# Annealer_PCB.net
KiCad netlist of a schematic drawn in EAGLE
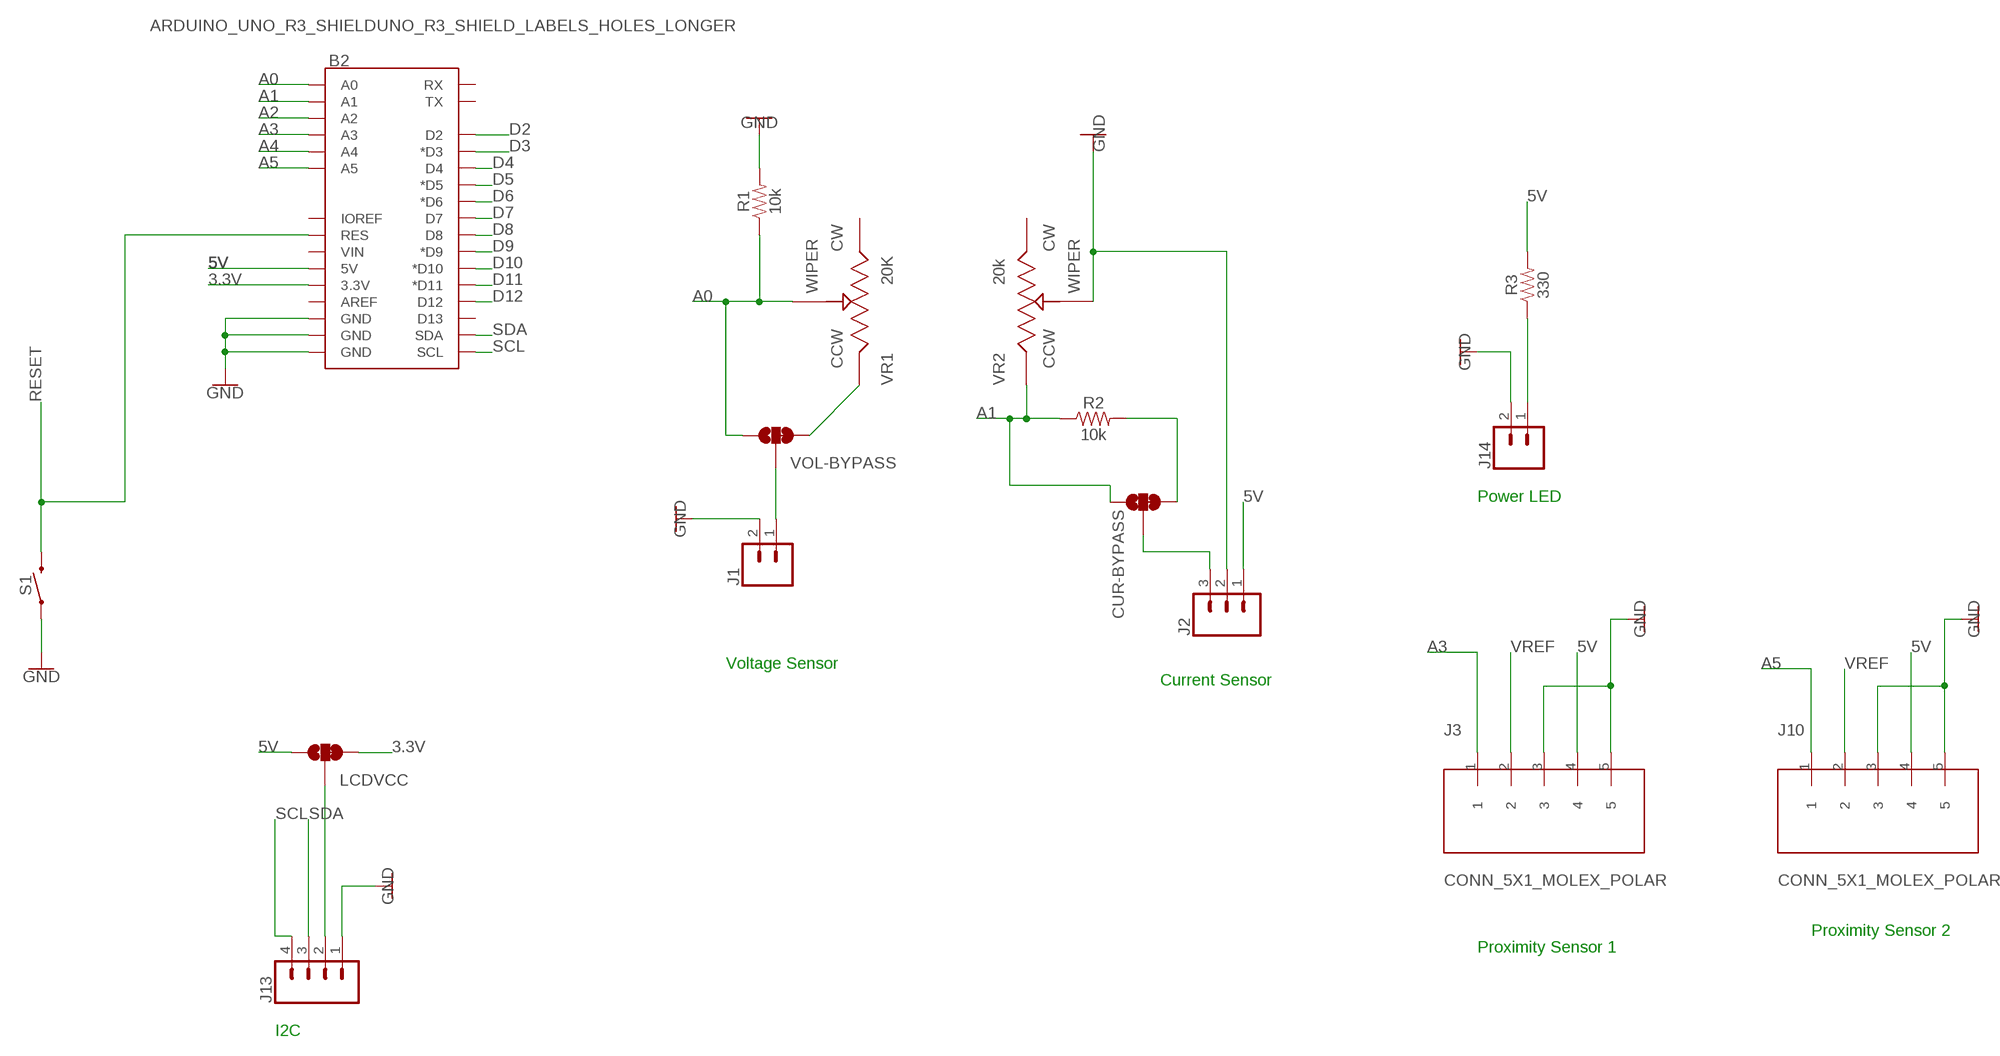
[diagram p0: schematic, sheet 1]
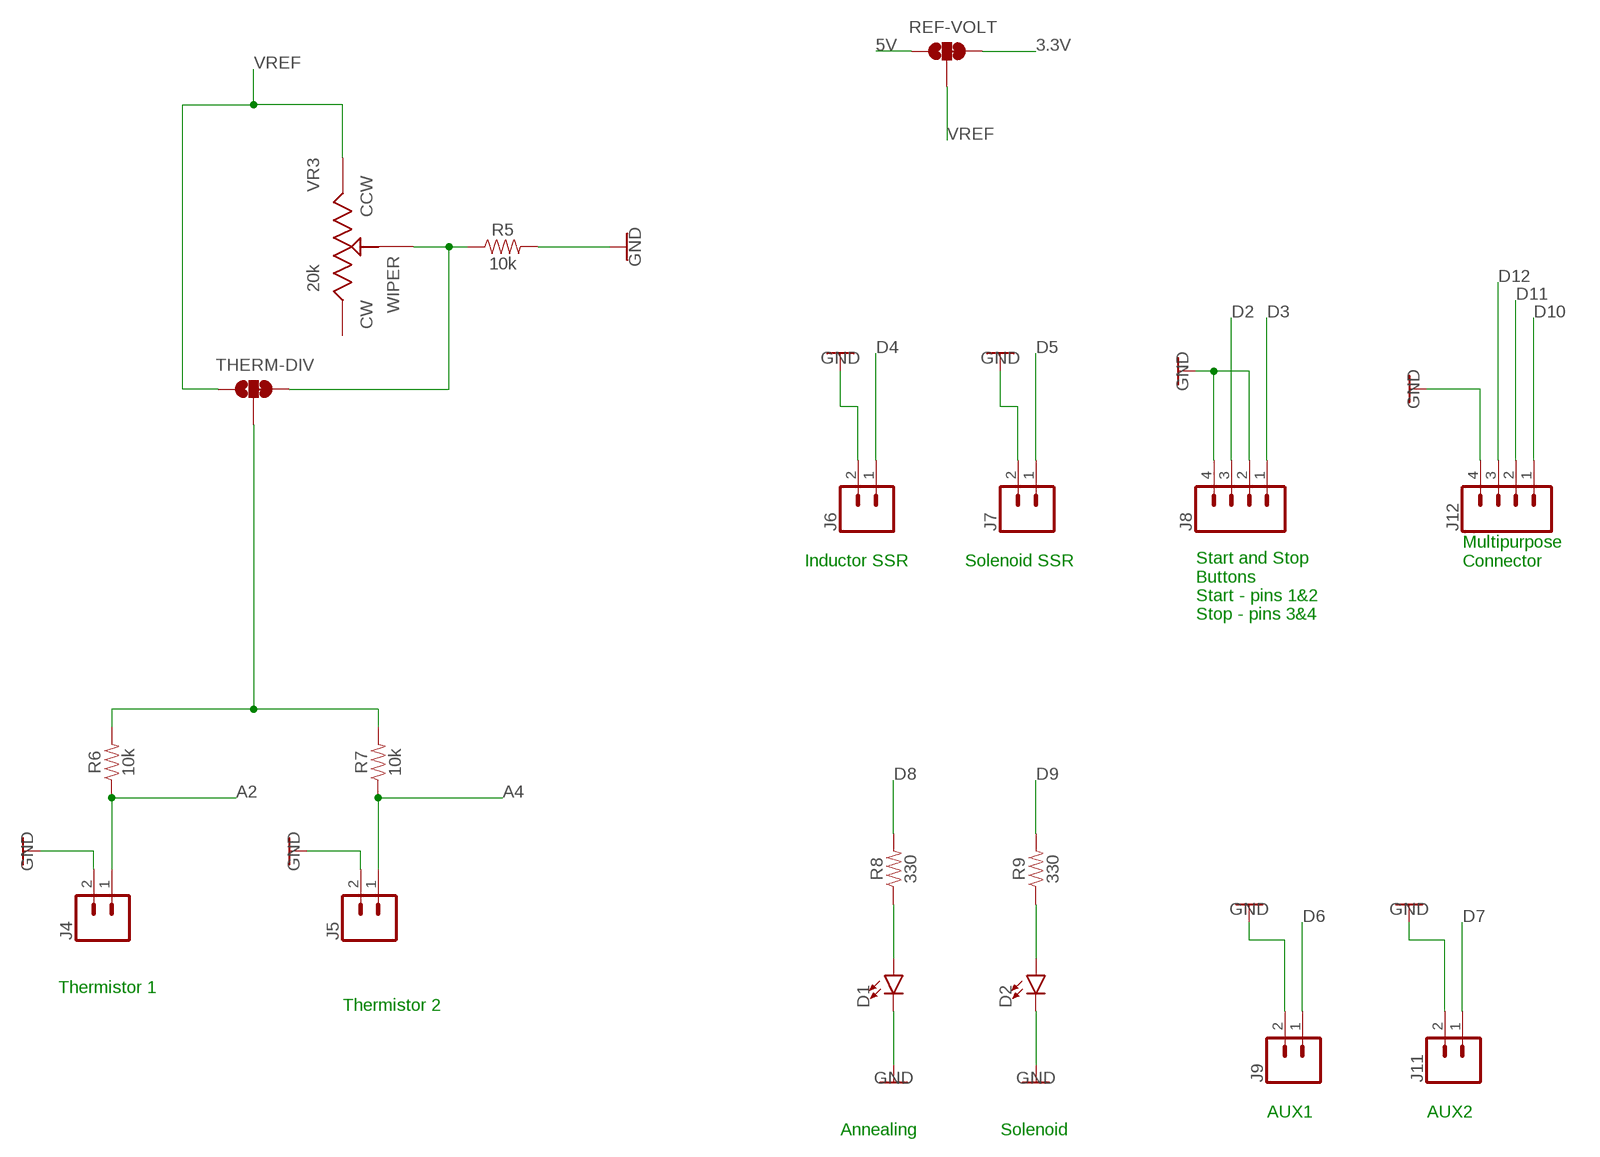
[diagram p1: schematic, sheet 2]

(export (version "E")
  (design (tool "Eeschema 10.0.6"))
  (components
    (comp (ref "D1")
      (value "LED5MM")
      (footprint "eagle-import:LED_5MM")
      (libsource (lib "eagle-import") (part "LED5MM"))
    )
    (comp (ref "D2")
      (value "LED5MM")
      (footprint "eagle-import:LED_5MM")
      (libsource (lib "eagle-import") (part "LED5MM"))
    )
    (comp (ref "J4")
      (value "CONN_02POLAR")
      (footprint "eagle-import:MOLEX-1X2")
      (libsource (lib "eagle-import") (part "CONN_02POLAR"))
    )
    (comp (ref "J5")
      (value "CONN_02POLAR")
      (footprint "eagle-import:MOLEX-1X2")
      (libsource (lib "eagle-import") (part "CONN_02POLAR"))
    )
    (comp (ref "J6")
      (value "CONN_02POLAR")
      (footprint "eagle-import:MOLEX-1X2")
      (libsource (lib "eagle-import") (part "CONN_02POLAR"))
    )
    (comp (ref "J7")
      (value "CONN_02POLAR")
      (footprint "eagle-import:MOLEX-1X2")
      (libsource (lib "eagle-import") (part "CONN_02POLAR"))
    )
    (comp (ref "J8")
      (value "CONN_04POLAR")
      (footprint "eagle-import:MOLEX-1X4")
      (libsource (lib "eagle-import") (part "CONN_04POLAR"))
    )
    (comp (ref "J9")
      (value "CONN_02POLAR")
      (footprint "eagle-import:MOLEX-1X2")
      (libsource (lib "eagle-import") (part "CONN_02POLAR"))
    )
    (comp (ref "J11")
      (value "CONN_02POLAR")
      (footprint "eagle-import:MOLEX-1X2")
      (libsource (lib "eagle-import") (part "CONN_02POLAR"))
    )
    (comp (ref "J12")
      (value "CONN_04POLAR")
      (footprint "eagle-import:MOLEX-1X4")
      (libsource (lib "eagle-import") (part "CONN_04POLAR"))
    )
    (comp (ref "R5")
      (value "10k")
      (footprint "eagle-import:AXIAL-0.3")
      (libsource (lib "eagle-import") (part "10KOHM-HORIZ-1/4W-1%"))
    )
    (comp (ref "R6")
      (value "10k")
      (footprint "eagle-import:AXIAL-0.3")
      (libsource (lib "eagle-import") (part "10KOHM-HORIZ-1/4W-1%"))
    )
    (comp (ref "R7")
      (value "10k")
      (footprint "eagle-import:AXIAL-0.3")
      (libsource (lib "eagle-import") (part "10KOHM-HORIZ-1/4W-1%"))
    )
    (comp (ref "R8")
      (value "330")
      (footprint "eagle-import:AXIAL-0.3")
      (libsource (lib "eagle-import") (part "330OHM-HORIZ-1/10W-5%"))
    )
    (comp (ref "R9")
      (value "330")
      (footprint "eagle-import:AXIAL-0.3")
      (libsource (lib "eagle-import") (part "330OHM-HORIZ-1/10W-5%"))
    )
    (comp (ref "REF-VOLT")
      (value "JUMPER-SMT_3_1-NC_TRACE_SILK")
      (footprint "eagle-import:SMT-JUMPER_3_1-NC_TRACE_SILK")
      (libsource (lib "eagle-import") (part "JUMPER-SMT_3_1-NC_TRACE_SILK"))
    )
    (comp (ref "THERM-DIV")
      (value "JUMPER-SMT_3_1-NC_TRACE_SILK")
      (footprint "eagle-import:SMT-JUMPER_3_1-NC_TRACE_SILK")
      (libsource (lib "eagle-import") (part "JUMPER-SMT_3_1-NC_TRACE_SILK"))
    )
    (comp (ref "VR3")
      (value "20k")
      (footprint "eagle-import:W")
      (fields
        (field (name "MANUFACTURER") "Bourns Inc")
        (field (name "PART_NUMBER") "3296W-1-103LF")
        (field (name "POWER") "0.5W, 1/2W")
      )
      (libsource (lib "eagle-import") (part "3296?-W1-103LF"))
    )
    (comp (ref "B2")
      (value "ARDUINO_UNO_R3_SHIELDUNO_R3_SHIELD_LABELS_HOLES_LONGER")
      (footprint "eagle-import:UNO_R3_SHIELD_HOLES_LONGER")
      (libsource (lib "eagle-import") (part "ARDUINO_UNO_R3_SHIELDUNO_R3_SHIELD_LABELS_HOLES_LONGER"))
    )
    (comp (ref "CUR-BYPASS")
      (value "JUMPER-SMT_3_1-NC_TRACE_SILK")
      (footprint "eagle-import:SMT-JUMPER_3_1-NC_TRACE_SILK")
      (libsource (lib "eagle-import") (part "JUMPER-SMT_3_1-NC_TRACE_SILK"))
    )
    (comp (ref "J1")
      (value "CONN_02POLAR")
      (footprint "eagle-import:MOLEX-1X2")
      (libsource (lib "eagle-import") (part "CONN_02POLAR"))
    )
    (comp (ref "J2")
      (value "CONN_03POLAR")
      (footprint "eagle-import:MOLEX-1X3")
      (libsource (lib "eagle-import") (part "CONN_03POLAR"))
    )
    (comp (ref "J3")
      (value "CONN_5X1_MOLEX_POLAR")
      (footprint "eagle-import:MOLEX-5")
      (libsource (lib "eagle-import") (part "CONN_5X1_MOLEX_POLAR"))
    )
    (comp (ref "J10")
      (value "CONN_5X1_MOLEX_POLAR")
      (footprint "eagle-import:MOLEX-5")
      (libsource (lib "eagle-import") (part "CONN_5X1_MOLEX_POLAR"))
    )
    (comp (ref "J13")
      (value "CONN_04POLAR")
      (footprint "eagle-import:MOLEX-1X4")
      (libsource (lib "eagle-import") (part "CONN_04POLAR"))
    )
    (comp (ref "J14")
      (value "CONN_02POLAR")
      (footprint "eagle-import:MOLEX-1X2")
      (libsource (lib "eagle-import") (part "CONN_02POLAR"))
    )
    (comp (ref "LCDVCC")
      (value "JUMPER-SMT_3_1-NC_TRACE_SILK")
      (footprint "eagle-import:SMT-JUMPER_3_1-NC_TRACE_SILK")
      (libsource (lib "eagle-import") (part "JUMPER-SMT_3_1-NC_TRACE_SILK"))
    )
    (comp (ref "R1")
      (value "10k")
      (footprint "eagle-import:AXIAL-0.3")
      (libsource (lib "eagle-import") (part "10KOHM-HORIZ-1/4W-1%"))
    )
    (comp (ref "R2")
      (value "10k")
      (footprint "eagle-import:AXIAL-0.3")
      (libsource (lib "eagle-import") (part "10KOHM-HORIZ-1/4W-1%"))
    )
    (comp (ref "R3")
      (value "330")
      (footprint "eagle-import:AXIAL-0.3")
      (libsource (lib "eagle-import") (part "330OHM-HORIZ-1/10W-5%"))
    )
    (comp (ref "S1")
      (value "MOMENTARY-SWITCH-SPST-PTH-6.0MM")
      (footprint "eagle-import:TACTILE_SWITCH_PTH_6.0MM")
      (libsource (lib "eagle-import") (part "MOMENTARY-SWITCH-SPST-PTH-6.0MM"))
    )
    (comp (ref "VOL-BYPASS")
      (value "JUMPER-SMT_3_1-NC_TRACE_SILK")
      (footprint "eagle-import:SMT-JUMPER_3_1-NC_TRACE_SILK")
      (libsource (lib "eagle-import") (part "JUMPER-SMT_3_1-NC_TRACE_SILK"))
    )
    (comp (ref "VR1")
      (value "20K")
      (footprint "eagle-import:W")
      (fields
        (field (name "MANUFACTURER") "Bourns Inc")
        (field (name "PART_NUMBER") "3296W-1-103LF")
        (field (name "POWER") "0.5W, 1/2W")
      )
      (libsource (lib "eagle-import") (part "3296?-W1-103LF"))
    )
    (comp (ref "VR2")
      (value "20k")
      (footprint "eagle-import:W")
      (fields
        (field (name "MANUFACTURER") "Bourns Inc")
        (field (name "PART_NUMBER") "3296W-1-103LF")
        (field (name "POWER") "0.5W, 1/2W")
      )
      (libsource (lib "eagle-import") (part "3296?-W1-103LF"))
    )
  )
  (nets
    (net (code "1") (name "3.3V") (class "Default")
      (node (ref "B2") (pin "3.3V") (pinfunction "3.3V_3.3V") (pintype "bidirectional"))
      (node (ref "LCDVCC") (pin "3") (pinfunction "3_3") (pintype "passive"))
      (node (ref "REF-VOLT") (pin "3") (pinfunction "3_3") (pintype "passive"))
    )
    (net (code "2") (name "5V") (class "Default")
      (node (ref "B2") (pin "5V") (pinfunction "5V_5V") (pintype "bidirectional"))
      (node (ref "J10") (pin "4") (pinfunction "4_4") (pintype "bidirectional"))
      (node (ref "J2") (pin "1") (pinfunction "1_1") (pintype "passive"))
      (node (ref "J3") (pin "4") (pinfunction "4_4") (pintype "bidirectional"))
      (node (ref "LCDVCC") (pin "1") (pinfunction "1_1") (pintype "passive"))
      (node (ref "R3") (pin "P$2") (pinfunction "2_P$2") (pintype "passive"))
      (node (ref "REF-VOLT") (pin "1") (pinfunction "1_1") (pintype "passive"))
    )
    (net (code "3") (name "A0") (class "Default")
      (node (ref "B2") (pin "A0") (pinfunction "A0_A0") (pintype "bidirectional"))
      (node (ref "R1") (pin "P$1") (pinfunction "1_P$1") (pintype "passive"))
      (node (ref "VOL-BYPASS") (pin "1") (pinfunction "1_1") (pintype "passive"))
      (node (ref "VR1") (pin "2") (pinfunction "2_2") (pintype "passive"))
    )
    (net (code "4") (name "A1") (class "Default")
      (node (ref "B2") (pin "A1") (pinfunction "A1_A1") (pintype "bidirectional"))
      (node (ref "CUR-BYPASS") (pin "1") (pinfunction "1_1") (pintype "passive"))
      (node (ref "R2") (pin "P$1") (pinfunction "1_P$1") (pintype "passive"))
      (node (ref "VR2") (pin "1") (pinfunction "1_1") (pintype "passive"))
    )
    (net (code "5") (name "A2") (class "Default")
      (node (ref "B2") (pin "A2") (pinfunction "A2_A2") (pintype "bidirectional"))
      (node (ref "J4") (pin "1") (pinfunction "1_1") (pintype "passive"))
      (node (ref "R6") (pin "P$1") (pinfunction "1_P$1") (pintype "passive"))
    )
    (net (code "6") (name "A3") (class "Default")
      (node (ref "B2") (pin "A3") (pinfunction "A3_A3") (pintype "bidirectional"))
      (node (ref "J3") (pin "1") (pinfunction "1_1") (pintype "bidirectional"))
    )
    (net (code "7") (name "A4") (class "Default")
      (node (ref "B2") (pin "A4") (pinfunction "A4_A4") (pintype "bidirectional"))
      (node (ref "J5") (pin "1") (pinfunction "1_1") (pintype "passive"))
      (node (ref "R7") (pin "P$1") (pinfunction "1_P$1") (pintype "passive"))
    )
    (net (code "8") (name "A5") (class "Default")
      (node (ref "B2") (pin "A5") (pinfunction "A5_A5") (pintype "bidirectional"))
      (node (ref "J10") (pin "1") (pinfunction "1_1") (pintype "bidirectional"))
    )
    (net (code "9") (name "D2") (class "Default")
      (node (ref "B2") (pin "D2") (pinfunction "D2_D2") (pintype "bidirectional"))
      (node (ref "J8") (pin "3") (pinfunction "3_3") (pintype "passive"))
    )
    (net (code "10") (name "D3") (class "Default")
      (node (ref "B2") (pin "D3") (pinfunction "*D3_D3") (pintype "bidirectional"))
      (node (ref "J8") (pin "1") (pinfunction "1_1") (pintype "passive"))
    )
    (net (code "11") (name "D4") (class "Default")
      (node (ref "B2") (pin "D4") (pinfunction "D4_D4") (pintype "bidirectional"))
      (node (ref "J6") (pin "1") (pinfunction "1_1") (pintype "passive"))
    )
    (net (code "12") (name "D5") (class "Default")
      (node (ref "B2") (pin "D5") (pinfunction "*D5_D5") (pintype "bidirectional"))
      (node (ref "J7") (pin "1") (pinfunction "1_1") (pintype "passive"))
    )
    (net (code "13") (name "D6") (class "Default")
      (node (ref "B2") (pin "D6") (pinfunction "*D6_D6") (pintype "bidirectional"))
      (node (ref "J9") (pin "1") (pinfunction "1_1") (pintype "passive"))
    )
    (net (code "14") (name "D7") (class "Default")
      (node (ref "B2") (pin "D7") (pinfunction "D7_D7") (pintype "bidirectional"))
      (node (ref "J11") (pin "1") (pinfunction "1_1") (pintype "passive"))
    )
    (net (code "15") (name "D8") (class "Default")
      (node (ref "B2") (pin "D8") (pinfunction "D8_D8") (pintype "bidirectional"))
      (node (ref "R8") (pin "P$2") (pinfunction "2_P$2") (pintype "passive"))
    )
    (net (code "16") (name "D9") (class "Default")
      (node (ref "B2") (pin "D9") (pinfunction "*D9_D9") (pintype "bidirectional"))
      (node (ref "R9") (pin "P$2") (pinfunction "2_P$2") (pintype "passive"))
    )
    (net (code "17") (name "D10") (class "Default")
      (node (ref "B2") (pin "D10") (pinfunction "*D10_D10") (pintype "bidirectional"))
      (node (ref "J12") (pin "1") (pinfunction "1_1") (pintype "passive"))
    )
    (net (code "18") (name "D11") (class "Default")
      (node (ref "B2") (pin "D11") (pinfunction "*D11_D11") (pintype "bidirectional"))
      (node (ref "J12") (pin "2") (pinfunction "2_2") (pintype "passive"))
    )
    (net (code "19") (name "D12") (class "Default")
      (node (ref "B2") (pin "D12") (pinfunction "D12_D12") (pintype "bidirectional"))
      (node (ref "J12") (pin "3") (pinfunction "3_3") (pintype "passive"))
    )
    (net (code "20") (name "GND") (class "Default")
      (node (ref "B2") (pin "GND@0") (pinfunction "GND_GND@0") (pintype "bidirectional"))
      (node (ref "B2") (pin "GND@1") (pinfunction "GND_GND@1") (pintype "bidirectional"))
      (node (ref "B2") (pin "GND@2") (pinfunction "GND_GND@2") (pintype "bidirectional"))
      (node (ref "D1") (pin "K") (pinfunction "C_K") (pintype "passive"))
      (node (ref "D2") (pin "K") (pinfunction "C_K") (pintype "passive"))
      (node (ref "J1") (pin "2") (pinfunction "2_2") (pintype "passive"))
      (node (ref "J10") (pin "3") (pinfunction "3_3") (pintype "bidirectional"))
      (node (ref "J10") (pin "5") (pinfunction "5_5") (pintype "bidirectional"))
      (node (ref "J11") (pin "2") (pinfunction "2_2") (pintype "passive"))
      (node (ref "J12") (pin "4") (pinfunction "4_4") (pintype "passive"))
      (node (ref "J13") (pin "1") (pinfunction "1_1") (pintype "passive"))
      (node (ref "J14") (pin "2") (pinfunction "2_2") (pintype "passive"))
      (node (ref "J2") (pin "2") (pinfunction "2_2") (pintype "passive"))
      (node (ref "J3") (pin "3") (pinfunction "3_3") (pintype "bidirectional"))
      (node (ref "J3") (pin "5") (pinfunction "5_5") (pintype "bidirectional"))
      (node (ref "J4") (pin "2") (pinfunction "2_2") (pintype "passive"))
      (node (ref "J5") (pin "2") (pinfunction "2_2") (pintype "passive"))
      (node (ref "J6") (pin "2") (pinfunction "2_2") (pintype "passive"))
      (node (ref "J7") (pin "2") (pinfunction "2_2") (pintype "passive"))
      (node (ref "J8") (pin "2") (pinfunction "2_2") (pintype "passive"))
      (node (ref "J8") (pin "4") (pinfunction "4_4") (pintype "passive"))
      (node (ref "J9") (pin "2") (pinfunction "2_2") (pintype "passive"))
      (node (ref "R1") (pin "P$2") (pinfunction "2_P$2") (pintype "passive"))
      (node (ref "R5") (pin "P$2") (pinfunction "2_P$2") (pintype "passive"))
      (node (ref "S1") (pin "1") (pinfunction "1_1") (pintype "passive"))
      (node (ref "VR2") (pin "2") (pinfunction "2_2") (pintype "passive"))
    )
    (net (code "21") (name "Net-(CUR-BYPASS-Pad2)") (class "Default")
      (node (ref "CUR-BYPASS") (pin "2") (pinfunction "2_2") (pintype "passive"))
      (node (ref "J2") (pin "3") (pinfunction "3_3") (pintype "passive"))
    )
    (net (code "22") (name "Net-(J1-Pad1)") (class "Default")
      (node (ref "J1") (pin "1") (pinfunction "1_1") (pintype "passive"))
      (node (ref "VOL-BYPASS") (pin "2") (pinfunction "2_2") (pintype "passive"))
    )
    (net (code "23") (name "Net-(J13-Pad2)") (class "Default")
      (node (ref "J13") (pin "2") (pinfunction "2_2") (pintype "passive"))
      (node (ref "LCDVCC") (pin "2") (pinfunction "2_2") (pintype "passive"))
    )
    (net (code "24") (name "Net-(R2-2)") (class "Default")
      (node (ref "CUR-BYPASS") (pin "3") (pinfunction "3_3") (pintype "passive"))
      (node (ref "R2") (pin "P$2") (pinfunction "2_P$2") (pintype "passive"))
    )
    (net (code "25") (name "Net-(R3-1)") (class "Default")
      (node (ref "J14") (pin "1") (pinfunction "1_1") (pintype "passive"))
      (node (ref "R3") (pin "P$1") (pinfunction "1_P$1") (pintype "passive"))
    )
    (net (code "26") (name "Net-(R5-1)") (class "Default")
      (node (ref "R5") (pin "P$1") (pinfunction "1_P$1") (pintype "passive"))
      (node (ref "THERM-DIV") (pin "3") (pinfunction "3_3") (pintype "passive"))
      (node (ref "VR3") (pin "2") (pinfunction "2_2") (pintype "passive"))
    )
    (net (code "27") (name "Net-(R6-2)") (class "Default")
      (node (ref "R6") (pin "P$2") (pinfunction "2_P$2") (pintype "passive"))
      (node (ref "R7") (pin "P$2") (pinfunction "2_P$2") (pintype "passive"))
      (node (ref "THERM-DIV") (pin "2") (pinfunction "2_2") (pintype "passive"))
    )
    (net (code "28") (name "Net-(R8-1)") (class "Default")
      (node (ref "D1") (pin "A") (pinfunction "A_A") (pintype "passive"))
      (node (ref "R8") (pin "P$1") (pinfunction "1_P$1") (pintype "passive"))
    )
    (net (code "29") (name "Net-(R9-1)") (class "Default")
      (node (ref "D2") (pin "A") (pinfunction "A_A") (pintype "passive"))
      (node (ref "R9") (pin "P$1") (pinfunction "1_P$1") (pintype "passive"))
    )
    (net (code "30") (name "Net-(VOL-BYPASS-Pad3)") (class "Default")
      (node (ref "VOL-BYPASS") (pin "3") (pinfunction "3_3") (pintype "passive"))
      (node (ref "VR1") (pin "1") (pinfunction "1_1") (pintype "passive"))
    )
    (net (code "31") (name "RESET") (class "Default")
      (node (ref "B2") (pin "RES") (pinfunction "RES_RES") (pintype "bidirectional"))
      (node (ref "S1") (pin "3") (pinfunction "2_3") (pintype "passive"))
    )
    (net (code "32") (name "SCL") (class "Default")
      (node (ref "B2") (pin "SCL") (pinfunction "SCL_SCL") (pintype "bidirectional"))
      (node (ref "J13") (pin "4") (pinfunction "4_4") (pintype "passive"))
    )
    (net (code "33") (name "SDA") (class "Default")
      (node (ref "B2") (pin "SDA") (pinfunction "SDA_SDA") (pintype "bidirectional"))
      (node (ref "J13") (pin "3") (pinfunction "3_3") (pintype "passive"))
    )
    (net (code "34") (name "VREF") (class "Default")
      (node (ref "J10") (pin "2") (pinfunction "2_2") (pintype "bidirectional"))
      (node (ref "J3") (pin "2") (pinfunction "2_2") (pintype "bidirectional"))
      (node (ref "REF-VOLT") (pin "2") (pinfunction "2_2") (pintype "passive"))
      (node (ref "THERM-DIV") (pin "1") (pinfunction "1_1") (pintype "passive"))
      (node (ref "VR3") (pin "1") (pinfunction "1_1") (pintype "passive"))
    )
    (net (code "35") (name "unconnected-(B2-PadAREF)") (class "Default")
      (node (ref "B2") (pin "AREF") (pinfunction "AREF_AREF") (pintype "bidirectional"))
    )
    (net (code "36") (name "unconnected-(B2-PadD13)") (class "Default")
      (node (ref "B2") (pin "D13") (pinfunction "D13_D13") (pintype "bidirectional"))
    )
    (net (code "37") (name "unconnected-(B2-PadIOREF)") (class "Default")
      (node (ref "B2") (pin "IOREF") (pinfunction "IOREF_IOREF") (pintype "bidirectional"))
    )
    (net (code "38") (name "unconnected-(B2-PadRX)") (class "Default")
      (node (ref "B2") (pin "RX") (pinfunction "RX_RX") (pintype "bidirectional"))
    )
    (net (code "39") (name "unconnected-(B2-PadTX)") (class "Default")
      (node (ref "B2") (pin "TX") (pinfunction "TX_TX") (pintype "bidirectional"))
    )
    (net (code "40") (name "unconnected-(B2-PadVIN)") (class "Default")
      (node (ref "B2") (pin "VIN") (pinfunction "VIN_VIN") (pintype "bidirectional"))
    )
    (net (code "41") (name "unconnected-(VR1-Pad3)") (class "Default")
      (node (ref "VR1") (pin "3") (pinfunction "3_3") (pintype "passive"))
    )
    (net (code "42") (name "unconnected-(VR2-Pad3)") (class "Default")
      (node (ref "VR2") (pin "3") (pinfunction "3_3") (pintype "passive"))
    )
    (net (code "43") (name "unconnected-(VR3-Pad3)") (class "Default")
      (node (ref "VR3") (pin "3") (pinfunction "3_3") (pintype "passive"))
    )
  )
)
